# encoder.net
KiCad netlist of a schematic drawn in Altium Designer
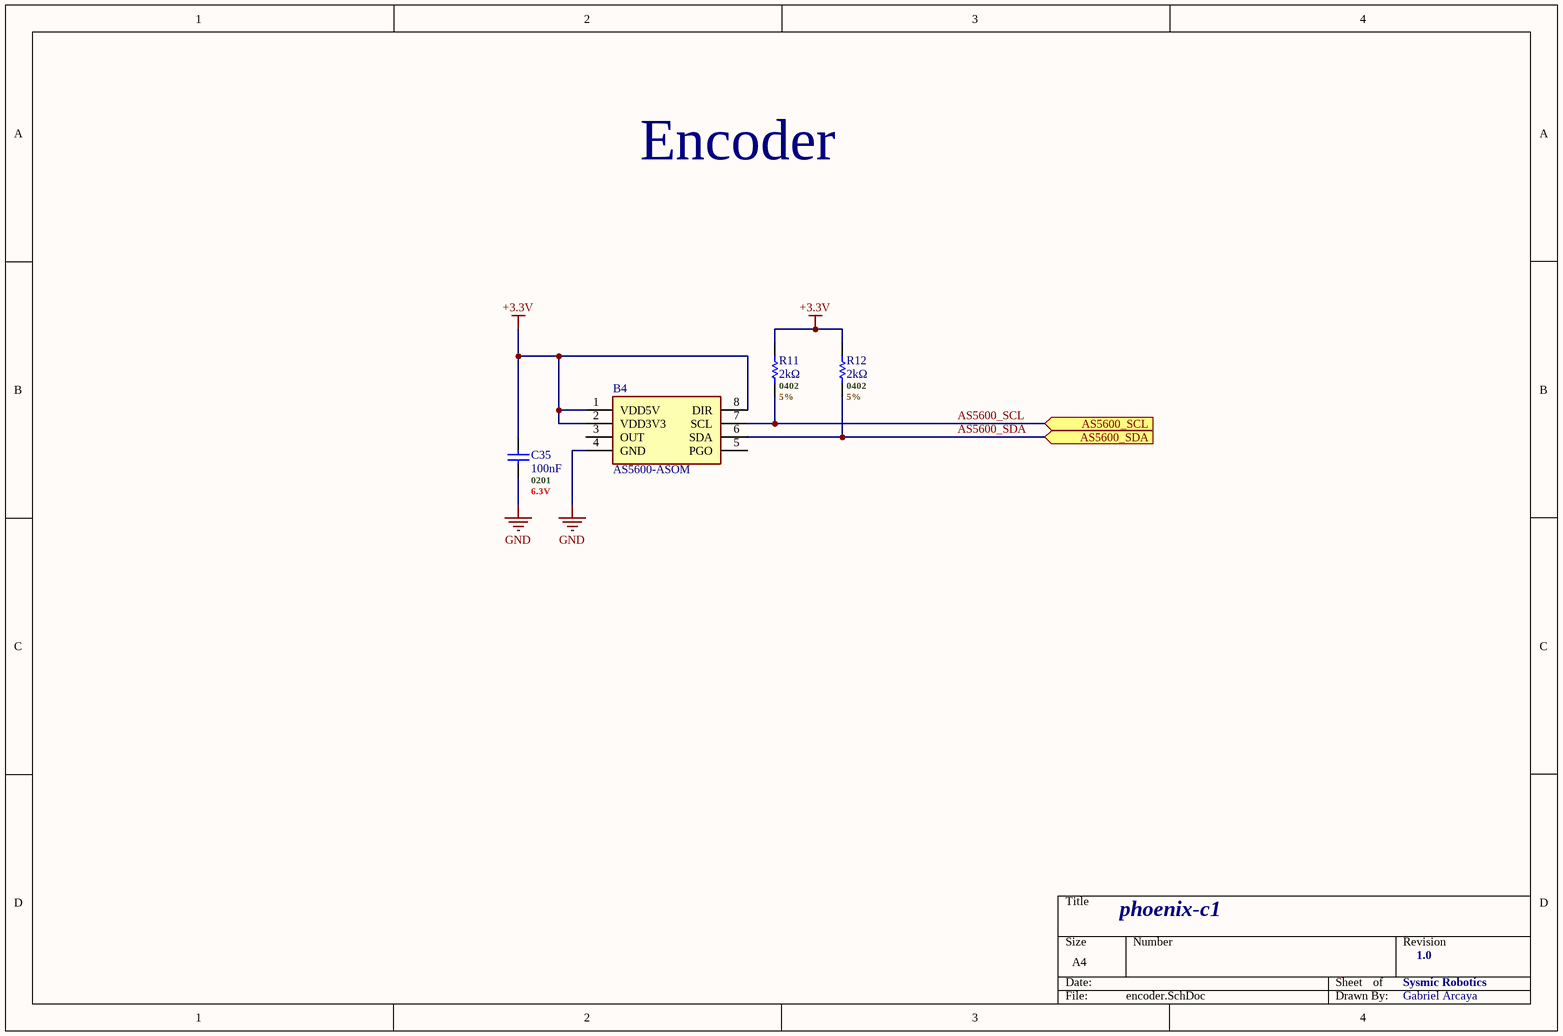
[diagram p0: encoder.SchDoc]

(export (version "E")
  (design (tool "Eeschema 10.0.6"))
  (components
    (comp (ref "B4")
      (value "AS5600-ASOM")
      (footprint "SOIC-8 - OSRAM")
      (description "IC SENSOR MAG ROTARY 12BIT 8SOIC")
      (fields (field (name "MOUSER PART NUMBER") "985-AS5600-ASOM"))
      (libsource (lib "IC - AS5600-ASOM") (part "AS5600-ASOM"))
    )
    (comp (ref "C35")
      (value "100nF")
      (footprint "C0201 - MURATA")
      (fields
        (field (name "MANUFACTURER") "Murata")
        (field (name "MANUFACTURER PART NUMBER") "GRT033R60J104KE01J")
        (field (name "TOLERANCE") "10%")
        (field (name ".CASE/PACKAGE") "0201")
        (field (name ".VOLTAGE RATING (DC)") "6.3V")
      )
      (libsource (lib "CAP - GRT033R60J104KE01J") (part "GRT033R60J104KE01J"))
    )
    (comp (ref "R11")
      (value "2kΩ")
      (footprint "R0402 - YAGEO")
      (description "Anti-Sulfurated Chip Resistor Thick Film 0402 2kOhm 5% Paper T/R")
      (fields
        (field (name "MANUFACTURER") "Yageo Group")
        (field (name "MANUFACTURER PART NUMBER") "AF0402JR-072KL")
        (field (name ".CASE/PACKAGE") "0402")
        (field (name ".TOLERANCE") "5%")
      )
      (libsource (lib "RES - AF024JR-0722KL") (part "AF0402JR-072KL"))
    )
    (comp (ref "R12")
      (value "2kΩ")
      (footprint "R0402 - YAGEO")
      (description "Anti-Sulfurated Chip Resistor Thick Film 0402 2kOhm 5% Paper T/R")
      (fields
        (field (name "MANUFACTURER") "Yageo Group")
        (field (name "MANUFACTURER PART NUMBER") "AF0402JR-072KL")
        (field (name ".CASE/PACKAGE") "0402")
        (field (name ".TOLERANCE") "5%")
      )
      (libsource (lib "RES - AF024JR-0722KL") (part "AF0402JR-072KL"))
    )
  )
  (nets
    (net (code "1") (name "+3.3V") (class "Default")
      (node (ref "B4") (pin "1") (pinfunction "VDD5V_1") (pintype "passive"))
      (node (ref "B4") (pin "2") (pinfunction "VDD3V3_2") (pintype "passive"))
      (node (ref "B4") (pin "8") (pinfunction "DIR_8") (pintype "passive"))
      (node (ref "C35") (pin "2") (pinfunction "2_2") (pintype "passive"))
      (node (ref "R11") (pin "2") (pinfunction "2_2") (pintype "passive"))
      (node (ref "R12") (pin "2") (pinfunction "2_2") (pintype "passive"))
    )
    (net (code "3") (name "/AS5600_SCL") (class "Default")
      (node (ref "B4") (pin "7") (pinfunction "SCL_7") (pintype "passive"))
      (node (ref "R11") (pin "1") (pinfunction "1_1") (pintype "passive"))
    )
    (net (code "4") (name "/AS5600_SDA") (class "Default")
      (node (ref "B4") (pin "6") (pinfunction "SDA_6") (pintype "passive"))
      (node (ref "R12") (pin "1") (pinfunction "1_1") (pintype "passive"))
    )
    (net (code "5") (name "GND") (class "Default")
      (node (ref "B4") (pin "4") (pinfunction "GND_4") (pintype "passive"))
      (node (ref "C35") (pin "1") (pinfunction "1_1") (pintype "passive"))
    )
    (net (code "6") (name "unconnected-(B4-OUT-Pad3)") (class "Default")
      (node (ref "B4") (pin "3") (pinfunction "OUT_3") (pintype "passive"))
    )
    (net (code "7") (name "unconnected-(B4-PGO-Pad5)") (class "Default")
      (node (ref "B4") (pin "5") (pinfunction "PGO_5") (pintype "passive"))
    )
  )
)
